# explorator_mainboard_v2_58mm_1_1.net
KiCad netlist of a schematic drawn in EAGLE
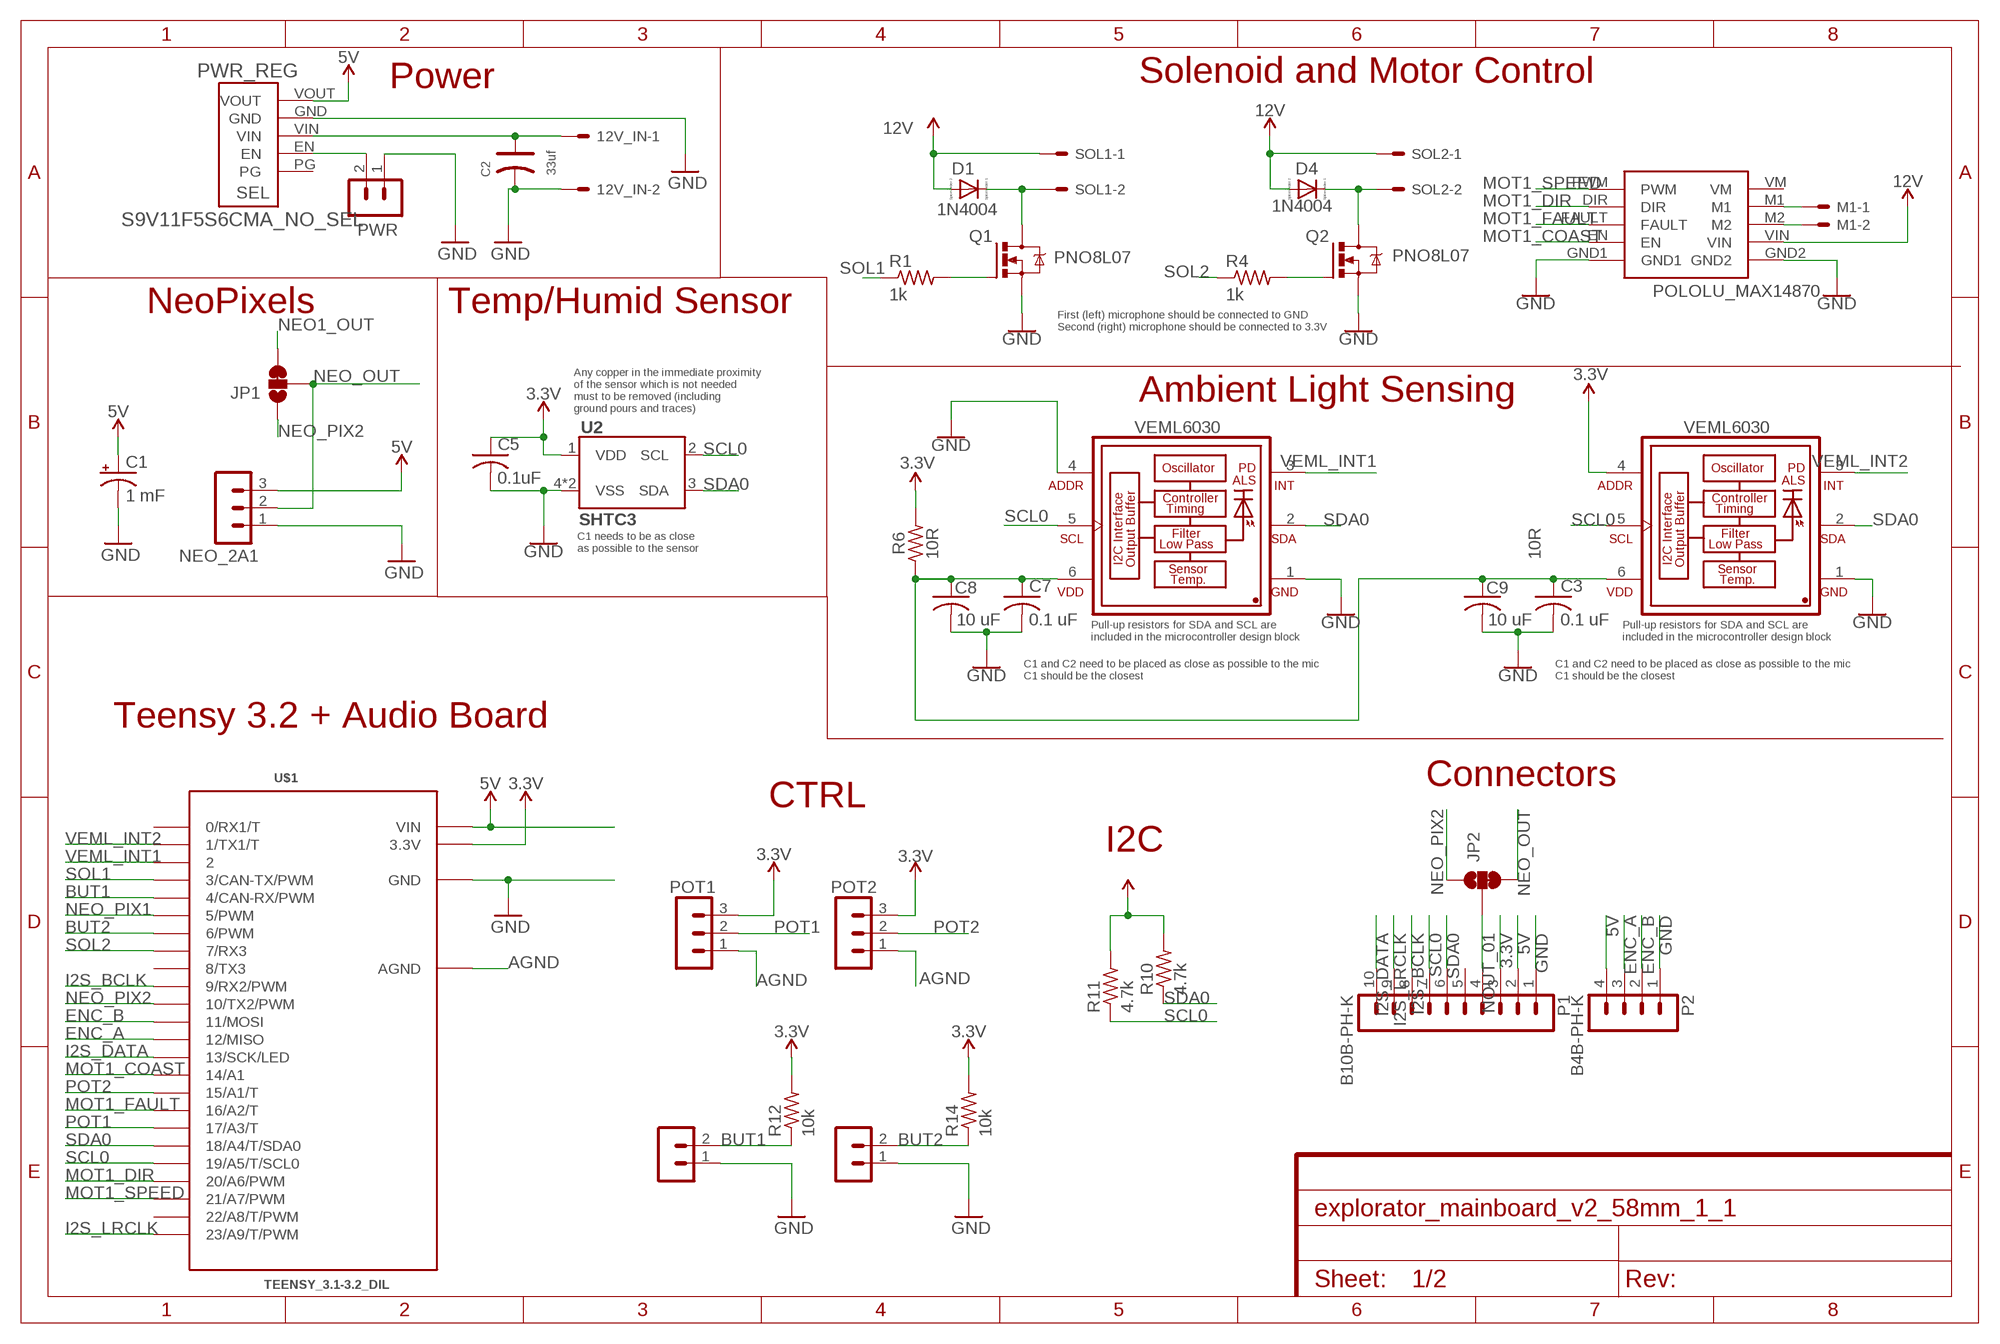
[diagram p0: schematic, sheet 1]
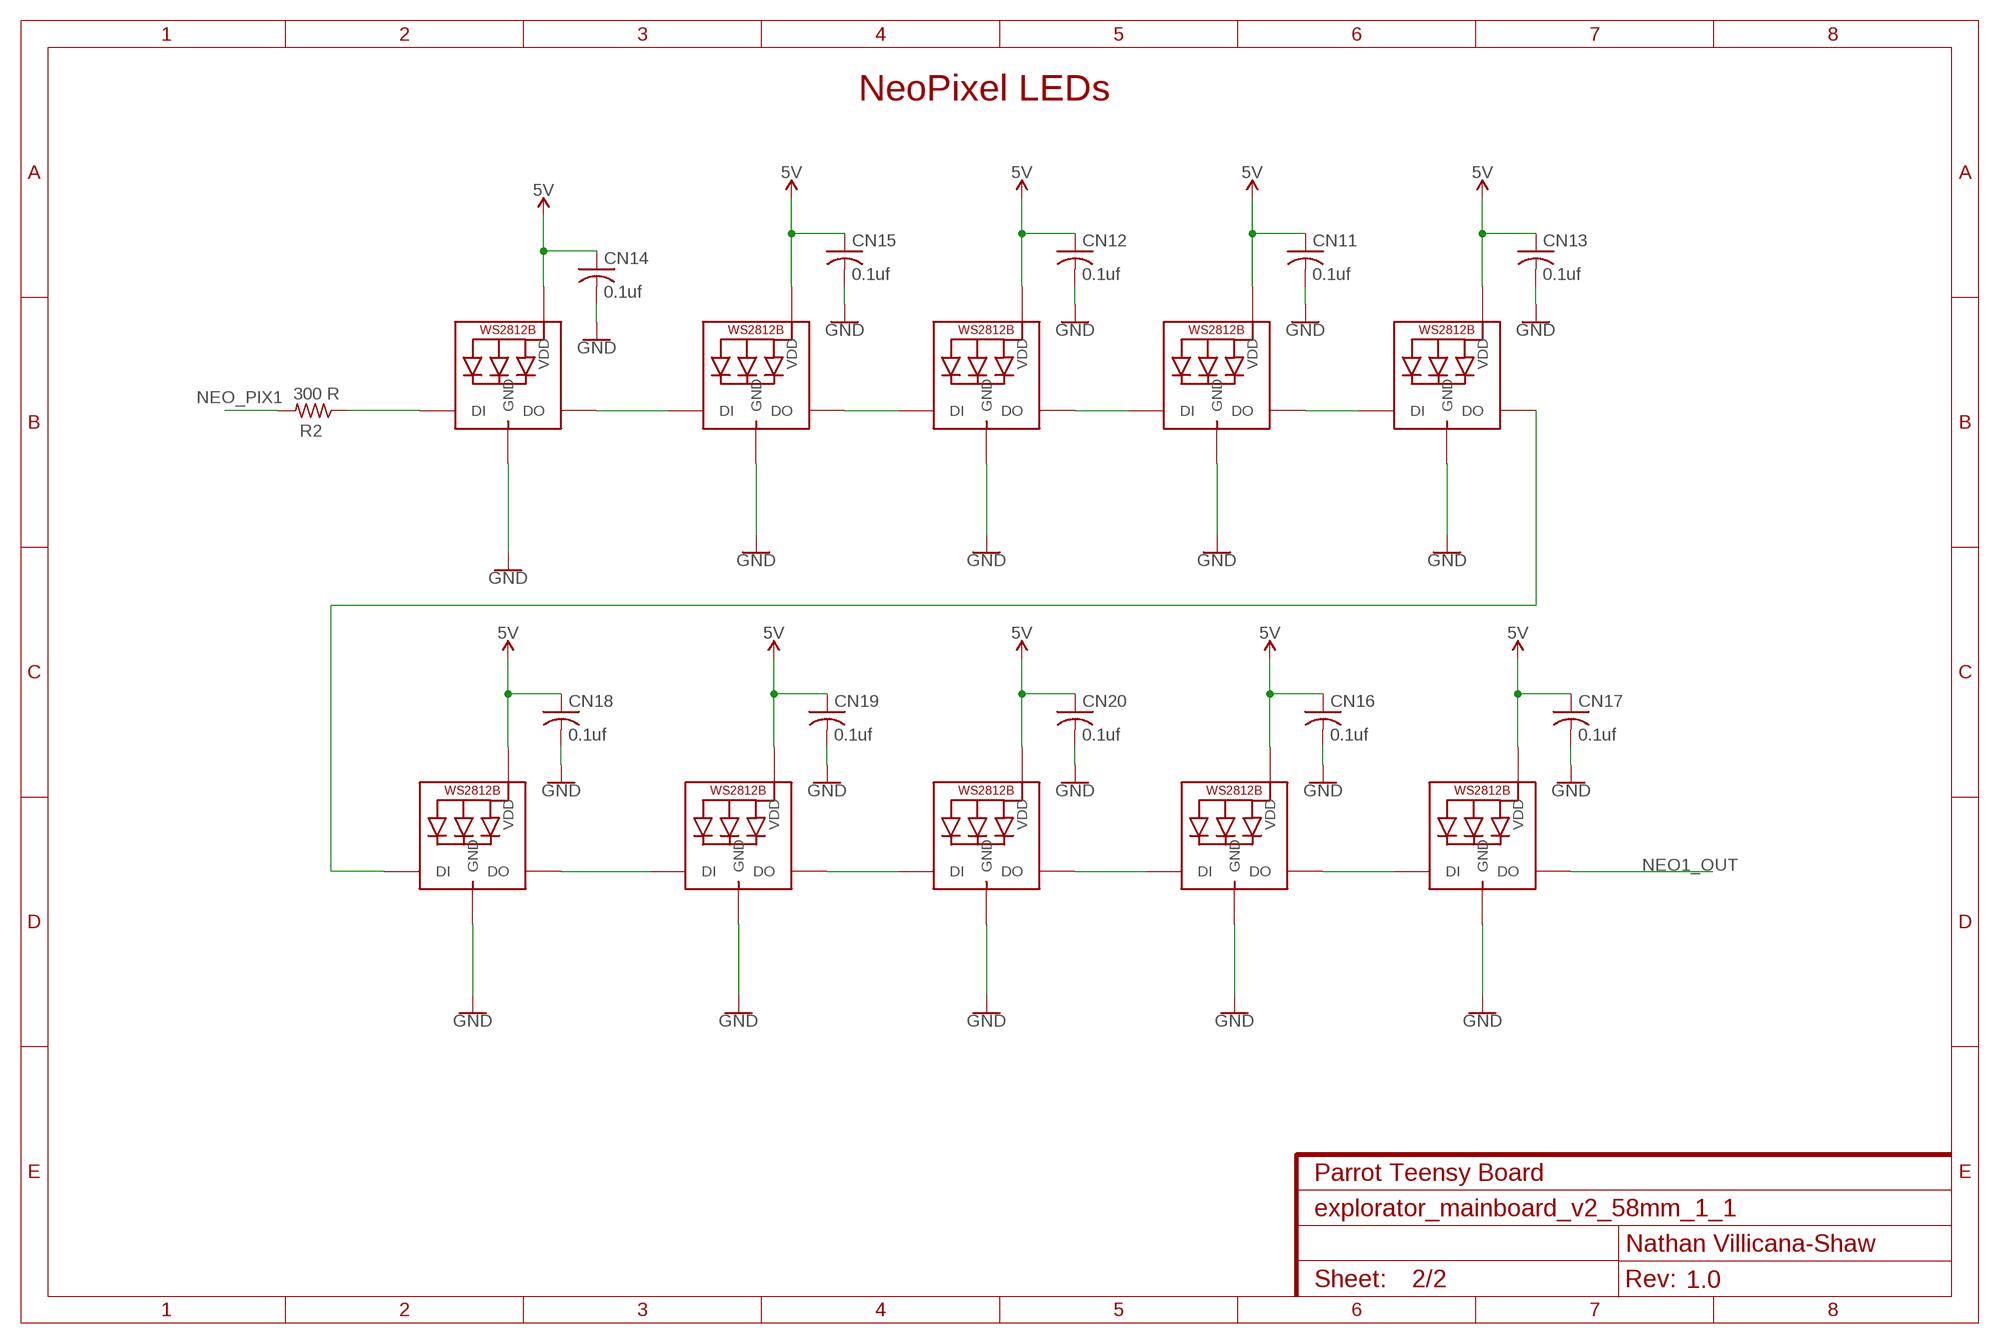
[diagram p1: schematic, sheet 2]

(export (version "E")
  (design (tool "Eeschema 10.0.6"))
  (components
    (comp (ref "12V_IN")
      (value "5566-2")
      (footprint "eagle-import:5566-2")
      (fields (field (name "MF") "MOLEX"))
      (libsource (lib "eagle-import") (part "5566-2"))
    )
    (comp (ref "BUT1")
      (value "B2B-PH-K")
      (footprint "eagle-import:B2B-PH-K")
      (libsource (lib "eagle-import") (part "B2B-PH-K"))
    )
    (comp (ref "BUT2")
      (value "B2B-PH-K")
      (footprint "eagle-import:B2B-PH-K")
      (libsource (lib "eagle-import") (part "B2B-PH-K"))
    )
    (comp (ref "C1")
      (value "1 mF")
      (footprint "eagle-import:UD-10X10_NICHICON")
      (libsource (lib "eagle-import") (part "CPOL-USUD-10X10"))
    )
    (comp (ref "C2")
      (value "33uf")
      (footprint "eagle-import:PC-D5.3MM")
      (fields (field (name "MPN") "KS 100uF/16V"))
      (libsource (lib "eagle-import") (part "DIP-ALUMINUM-47UF-16V(D5-H7MM)"))
    )
    (comp (ref "C3")
      (value "0.1 uF")
      (footprint "eagle-import:C0805")
      (libsource (lib "eagle-import") (part "C-USC0805"))
    )
    (comp (ref "C5")
      (value "0.1uF")
      (footprint "eagle-import:C0805")
      (libsource (lib "eagle-import") (part "C-USC0805"))
    )
    (comp (ref "C7")
      (value "0.1 uF")
      (footprint "eagle-import:C0805")
      (libsource (lib "eagle-import") (part "C-USC0805"))
    )
    (comp (ref "C8")
      (value "10 uF")
      (footprint "eagle-import:C0805")
      (libsource (lib "eagle-import") (part "C-USC0805"))
    )
    (comp (ref "C9")
      (value "10 uF")
      (footprint "eagle-import:C0805")
      (libsource (lib "eagle-import") (part "C-USC0805"))
    )
    (comp (ref "D1")
      (value "1N4004")
      (footprint "eagle-import:DIODE_DO35-7")
      (libsource (lib "eagle-import") (part "DIODE_E-DO35-7"))
    )
    (comp (ref "D4")
      (value "1N4004")
      (footprint "eagle-import:DIODE_DO35-7")
      (libsource (lib "eagle-import") (part "DIODE_E-DO35-7"))
    )
    (comp (ref "JP1")
      (value "JUMPER-SMT_3_1-NC_TRACE_SILK")
      (footprint "eagle-import:SMT-JUMPER_3_1-NC_TRACE_SILK")
      (libsource (lib "eagle-import") (part "JUMPER-SMT_3_1-NC_TRACE_SILK"))
    )
    (comp (ref "JP2")
      (value "JUMPER-SMT_3_1-NC_TRACE_SILK")
      (footprint "eagle-import:SMT-JUMPER_3_1-NC_TRACE_SILK")
      (libsource (lib "eagle-import") (part "JUMPER-SMT_3_1-NC_TRACE_SILK"))
    )
    (comp (ref "M1")
      (value "5566-2")
      (footprint "eagle-import:5566-2")
      (fields (field (name "MF") "MOLEX"))
      (libsource (lib "eagle-import") (part "5566-2"))
    )
    (comp (ref "MOT1")
      (value "POLOLU_MAX14870")
      (footprint "eagle-import:POLOLU_MAX14870")
      (libsource (lib "eagle-import") (part "POLOLU_MAX14870"))
    )
    (comp (ref "NEO_2A1")
      (value "B3B-PH-K")
      (footprint "eagle-import:B3B-PH-K")
      (libsource (lib "eagle-import") (part "B3B-PH-K"))
    )
    (comp (ref "P1")
      (value "B10B-PH-K")
      (footprint "eagle-import:B10B-PH-K")
      (libsource (lib "eagle-import") (part "B10B-PH-K"))
    )
    (comp (ref "P2")
      (value "B4B-PH-K")
      (footprint "eagle-import:B4B-PH-K")
      (libsource (lib "eagle-import") (part "B4B-PH-K"))
    )
    (comp (ref "POT1")
      (value "B3B-PH-K")
      (footprint "eagle-import:B3B-PH-K")
      (libsource (lib "eagle-import") (part "B3B-PH-K"))
    )
    (comp (ref "POT2")
      (value "B3B-PH-K")
      (footprint "eagle-import:B3B-PH-K")
      (libsource (lib "eagle-import") (part "B3B-PH-K"))
    )
    (comp (ref "PWR")
      (value "B2B-PH-K")
      (footprint "eagle-import:B2B-PH-K")
      (libsource (lib "eagle-import") (part "B2B-PH-K"))
    )
    (comp (ref "PWR_REG")
      (value "S9V11F5S6CMA_NO_SEL")
      (footprint "eagle-import:S9V11F3S5CMA_NO_SEL")
      (libsource (lib "eagle-import") (part "S9V11F5S6CMA_NO_SEL"))
    )
    (comp (ref "Q1")
      (value "PNO8L07")
      (footprint "eagle-import:TO220BV")
      (libsource (lib "eagle-import") (part "IRF540"))
    )
    (comp (ref "Q2")
      (value "PNO8L07")
      (footprint "eagle-import:TO220BV")
      (libsource (lib "eagle-import") (part "IRF540"))
    )
    (comp (ref "R1")
      (value "1k")
      (footprint "eagle-import:R0805")
      (libsource (lib "eagle-import") (part "rcl_334_R-US_R0805"))
    )
    (comp (ref "R4")
      (value "1k")
      (footprint "eagle-import:R0805")
      (libsource (lib "eagle-import") (part "rcl_334_R-US_R0805"))
    )
    (comp (ref "R6")
      (value "10 R")
      (footprint "eagle-import:R0805")
      (libsource (lib "eagle-import") (part "R-US_R0805"))
    )
    (comp (ref "R10")
      (value "4.7k")
      (footprint "eagle-import:R0805")
      (libsource (lib "eagle-import") (part "rcl_334_R-US_R0805"))
    )
    (comp (ref "R11")
      (value "4.7k")
      (footprint "eagle-import:R0805")
      (libsource (lib "eagle-import") (part "rcl_334_R-US_R0805"))
    )
    (comp (ref "R12")
      (value "10k")
      (footprint "eagle-import:R0805")
      (libsource (lib "eagle-import") (part "rcl_334_R-US_R0805"))
    )
    (comp (ref "R14")
      (value "10k")
      (footprint "eagle-import:R0805")
      (libsource (lib "eagle-import") (part "rcl_334_R-US_R0805"))
    )
    (comp (ref "SOL1")
      (value "5566-2")
      (footprint "eagle-import:5566-2")
      (fields (field (name "MF") "MOLEX"))
      (libsource (lib "eagle-import") (part "5566-2"))
    )
    (comp (ref "SOL2")
      (value "5566-2")
      (footprint "eagle-import:5566-2")
      (fields (field (name "MF") "MOLEX"))
      (libsource (lib "eagle-import") (part "5566-2"))
    )
    (comp (ref "U$1")
      (value "TEENSY_3.1-3.2_DIL")
      (footprint "eagle-import:TEENSY_3.0-3.2&LC_DIL")
      (libsource (lib "eagle-import") (part "TEENSY_3.1-3.2_DIL"))
    )
    (comp (ref "U2")
      (value "SHTC3")
      (footprint "eagle-import:SHTC3")
      (libsource (lib "eagle-import") (part "SHTC3"))
    )
    (comp (ref "VMEL1")
      (value "VEML6030")
      (footprint "eagle-import:VISHAY_VEML6030_2X2X0.87")
      (fields (field (name "MF") "Vishay Semiconductor") (field (name "MP") "VEML6030-GS15"))
      (libsource (lib "eagle-import") (part "VEML6030-GS15"))
    )
    (comp (ref "VMEL2")
      (value "VEML6030")
      (footprint "eagle-import:VISHAY_VEML6030_2X2X0.87")
      (fields (field (name "MF") "Vishay Semiconductor") (field (name "MP") "VEML6030-GS15"))
      (libsource (lib "eagle-import") (part "VEML6030-GS15"))
    )
    (comp (ref "CN11")
      (value "0.1uf")
      (footprint "eagle-import:C0805K")
      (libsource (lib "eagle-import") (part "resistor_348_C-USC0805K"))
    )
    (comp (ref "CN12")
      (value "0.1uf")
      (footprint "eagle-import:C0805K")
      (libsource (lib "eagle-import") (part "resistor_348_C-USC0805K"))
    )
    (comp (ref "CN13")
      (value "0.1uf")
      (footprint "eagle-import:C0805K")
      (libsource (lib "eagle-import") (part "resistor_348_C-USC0805K"))
    )
    (comp (ref "CN14")
      (value "0.1uf")
      (footprint "eagle-import:C0805K")
      (libsource (lib "eagle-import") (part "resistor_348_C-USC0805K"))
    )
    (comp (ref "CN15")
      (value "0.1uf")
      (footprint "eagle-import:C0805K")
      (libsource (lib "eagle-import") (part "resistor_348_C-USC0805K"))
    )
    (comp (ref "CN16")
      (value "0.1uf")
      (footprint "eagle-import:C0805K")
      (libsource (lib "eagle-import") (part "resistor_348_C-USC0805K"))
    )
    (comp (ref "CN17")
      (value "0.1uf")
      (footprint "eagle-import:C0805K")
      (libsource (lib "eagle-import") (part "resistor_348_C-USC0805K"))
    )
    (comp (ref "CN18")
      (value "0.1uf")
      (footprint "eagle-import:C0805K")
      (libsource (lib "eagle-import") (part "resistor_348_C-USC0805K"))
    )
    (comp (ref "CN19")
      (value "0.1uf")
      (footprint "eagle-import:C0805K")
      (libsource (lib "eagle-import") (part "resistor_348_C-USC0805K"))
    )
    (comp (ref "CN20")
      (value "0.1uf")
      (footprint "eagle-import:C0805K")
      (libsource (lib "eagle-import") (part "resistor_348_C-USC0805K"))
    )
    (comp (ref "NEO11")
      (value "WS2812B5050")
      (footprint "eagle-import:WS2812B")
      (libsource (lib "eagle-import") (part "WS2812B5050"))
    )
    (comp (ref "NEO12")
      (value "WS2812B5050")
      (footprint "eagle-import:WS2812B")
      (libsource (lib "eagle-import") (part "WS2812B5050"))
    )
    (comp (ref "NEO13")
      (value "WS2812B5050")
      (footprint "eagle-import:WS2812B")
      (libsource (lib "eagle-import") (part "WS2812B5050"))
    )
    (comp (ref "NEO14")
      (value "WS2812B5050")
      (footprint "eagle-import:WS2812B")
      (libsource (lib "eagle-import") (part "WS2812B5050"))
    )
    (comp (ref "NEO15")
      (value "WS2812B5050")
      (footprint "eagle-import:WS2812B")
      (libsource (lib "eagle-import") (part "WS2812B5050"))
    )
    (comp (ref "NEO16")
      (value "WS2812B5050")
      (footprint "eagle-import:WS2812B")
      (libsource (lib "eagle-import") (part "WS2812B5050"))
    )
    (comp (ref "NEO17")
      (value "WS2812B5050")
      (footprint "eagle-import:WS2812B")
      (libsource (lib "eagle-import") (part "WS2812B5050"))
    )
    (comp (ref "NEO18")
      (value "WS2812B5050")
      (footprint "eagle-import:WS2812B")
      (libsource (lib "eagle-import") (part "WS2812B5050"))
    )
    (comp (ref "NEO19")
      (value "WS2812B5050")
      (footprint "eagle-import:WS2812B")
      (libsource (lib "eagle-import") (part "WS2812B5050"))
    )
    (comp (ref "NEO20")
      (value "WS2812B5050")
      (footprint "eagle-import:WS2812B")
      (libsource (lib "eagle-import") (part "WS2812B5050"))
    )
    (comp (ref "R2")
      (value "300 R")
      (footprint "eagle-import:R0805")
      (libsource (lib "eagle-import") (part "R-US_R0805"))
    )
  )
  (nets
    (net (code "1") (name "3.3V") (class "Default")
      (node (ref "C5") (pin "1") (pinfunction "1_1") (pintype "passive"))
      (node (ref "P1") (pin "3") (pinfunction "3_3") (pintype "passive"))
      (node (ref "POT1") (pin "3") (pinfunction "3_3") (pintype "passive"))
      (node (ref "POT2") (pin "3") (pinfunction "3_3") (pintype "passive"))
      (node (ref "R10") (pin "2") (pinfunction "2_2") (pintype "passive"))
      (node (ref "R11") (pin "2") (pinfunction "2_2") (pintype "passive"))
      (node (ref "R12") (pin "2") (pinfunction "2_2") (pintype "passive"))
      (node (ref "R14") (pin "2") (pinfunction "2_2") (pintype "passive"))
      (node (ref "R6") (pin "2") (pinfunction "2_2") (pintype "passive"))
      (node (ref "U$1") (pin "3.3V") (pinfunction "3.3V_3.3V") (pintype "power_in"))
      (node (ref "U2") (pin "1") (pinfunction "VDD_1") (pintype "bidirectional"))
      (node (ref "VMEL2") (pin "4") (pinfunction "ADDR_4") (pintype "bidirectional"))
    )
    (net (code "2") (name "5V") (class "Default")
      (node (ref "C1") (pin "+") (pinfunction "+_+") (pintype "passive"))
      (node (ref "CN11") (pin "1") (pinfunction "1_1") (pintype "passive"))
      (node (ref "CN12") (pin "1") (pinfunction "1_1") (pintype "passive"))
      (node (ref "CN13") (pin "1") (pinfunction "1_1") (pintype "passive"))
      (node (ref "CN14") (pin "1") (pinfunction "1_1") (pintype "passive"))
      (node (ref "CN15") (pin "1") (pinfunction "1_1") (pintype "passive"))
      (node (ref "CN16") (pin "1") (pinfunction "1_1") (pintype "passive"))
      (node (ref "CN17") (pin "1") (pinfunction "1_1") (pintype "passive"))
      (node (ref "CN18") (pin "1") (pinfunction "1_1") (pintype "passive"))
      (node (ref "CN19") (pin "1") (pinfunction "1_1") (pintype "passive"))
      (node (ref "CN20") (pin "1") (pinfunction "1_1") (pintype "passive"))
      (node (ref "NEO11") (pin "1-VDD") (pinfunction "VDD_1-VDD") (pintype "power_in"))
      (node (ref "NEO12") (pin "1-VDD") (pinfunction "VDD_1-VDD") (pintype "power_in"))
      (node (ref "NEO13") (pin "1-VDD") (pinfunction "VDD_1-VDD") (pintype "power_in"))
      (node (ref "NEO14") (pin "1-VDD") (pinfunction "VDD_1-VDD") (pintype "power_in"))
      (node (ref "NEO15") (pin "1-VDD") (pinfunction "VDD_1-VDD") (pintype "power_in"))
      (node (ref "NEO16") (pin "1-VDD") (pinfunction "VDD_1-VDD") (pintype "power_in"))
      (node (ref "NEO17") (pin "1-VDD") (pinfunction "VDD_1-VDD") (pintype "power_in"))
      (node (ref "NEO18") (pin "1-VDD") (pinfunction "VDD_1-VDD") (pintype "power_in"))
      (node (ref "NEO19") (pin "1-VDD") (pinfunction "VDD_1-VDD") (pintype "power_in"))
      (node (ref "NEO20") (pin "1-VDD") (pinfunction "VDD_1-VDD") (pintype "power_in"))
      (node (ref "NEO_2A1") (pin "3") (pinfunction "3_3") (pintype "passive"))
      (node (ref "P1") (pin "2") (pinfunction "2_2") (pintype "passive"))
      (node (ref "P2") (pin "4") (pinfunction "4_4") (pintype "passive"))
      (node (ref "PWR_REG") (pin "VOUT") (pinfunction "VOUT_VOUT") (pintype "bidirectional"))
      (node (ref "U$1") (pin "VIN") (pinfunction "VIN_VIN") (pintype "power_in"))
    )
    (net (code "3") (name "12V") (class "Default")
      (node (ref "12V_IN") (pin "1") (pinfunction "S_1") (pintype "passive"))
      (node (ref "C2") (pin "+") (pinfunction "+_+") (pintype "passive"))
      (node (ref "D1") (pin "A") (pinfunction "C_A") (pintype "passive"))
      (node (ref "D4") (pin "A") (pinfunction "C_A") (pintype "passive"))
      (node (ref "MOT1") (pin "VIN") (pinfunction "VIN_VIN") (pintype "bidirectional"))
      (node (ref "PWR_REG") (pin "VIN") (pinfunction "VIN_VIN") (pintype "bidirectional"))
      (node (ref "SOL1") (pin "1") (pinfunction "S_1") (pintype "passive"))
      (node (ref "SOL2") (pin "1") (pinfunction "S_1") (pintype "passive"))
    )
    (net (code "4") (name "AGND") (class "Default")
      (node (ref "POT1") (pin "1") (pinfunction "1_1") (pintype "passive"))
      (node (ref "POT2") (pin "1") (pinfunction "1_1") (pintype "passive"))
      (node (ref "U$1") (pin "AGND") (pinfunction "AGND_AGND") (pintype "power_in"))
    )
    (net (code "5") (name "BUT1") (class "Default")
      (node (ref "BUT1") (pin "2") (pinfunction "2_2") (pintype "passive"))
      (node (ref "R12") (pin "1") (pinfunction "1_1") (pintype "passive"))
      (node (ref "U$1") (pin "4") (pinfunction "4/CAN-RX/PWM_4") (pintype "bidirectional"))
    )
    (net (code "6") (name "BUT2") (class "Default")
      (node (ref "BUT2") (pin "2") (pinfunction "2_2") (pintype "passive"))
      (node (ref "R14") (pin "1") (pinfunction "1_1") (pintype "passive"))
      (node (ref "U$1") (pin "6") (pinfunction "6/PWM_6") (pintype "bidirectional"))
    )
    (net (code "7") (name "ENC_A") (class "Default")
      (node (ref "P2") (pin "3") (pinfunction "3_3") (pintype "passive"))
      (node (ref "U$1") (pin "12") (pinfunction "12/MISO_12") (pintype "bidirectional"))
    )
    (net (code "8") (name "ENC_B") (class "Default")
      (node (ref "P2") (pin "2") (pinfunction "2_2") (pintype "passive"))
      (node (ref "U$1") (pin "11") (pinfunction "11/MOSI_11") (pintype "bidirectional"))
    )
    (net (code "9") (name "GND") (class "Default")
      (node (ref "12V_IN") (pin "2") (pinfunction "S_2") (pintype "passive"))
      (node (ref "BUT1") (pin "1") (pinfunction "1_1") (pintype "passive"))
      (node (ref "BUT2") (pin "1") (pinfunction "1_1") (pintype "passive"))
      (node (ref "C1") (pin "-") (pinfunction "-_-") (pintype "passive"))
      (node (ref "C2") (pin "-") (pinfunction "-_-") (pintype "passive"))
      (node (ref "C3") (pin "2") (pinfunction "2_2") (pintype "passive"))
      (node (ref "C5") (pin "2") (pinfunction "2_2") (pintype "passive"))
      (node (ref "C7") (pin "2") (pinfunction "2_2") (pintype "passive"))
      (node (ref "C8") (pin "2") (pinfunction "2_2") (pintype "passive"))
      (node (ref "C9") (pin "2") (pinfunction "2_2") (pintype "passive"))
      (node (ref "CN11") (pin "2") (pinfunction "2_2") (pintype "passive"))
      (node (ref "CN12") (pin "2") (pinfunction "2_2") (pintype "passive"))
      (node (ref "CN13") (pin "2") (pinfunction "2_2") (pintype "passive"))
      (node (ref "CN14") (pin "2") (pinfunction "2_2") (pintype "passive"))
      (node (ref "CN15") (pin "2") (pinfunction "2_2") (pintype "passive"))
      (node (ref "CN16") (pin "2") (pinfunction "2_2") (pintype "passive"))
      (node (ref "CN17") (pin "2") (pinfunction "2_2") (pintype "passive"))
      (node (ref "CN18") (pin "2") (pinfunction "2_2") (pintype "passive"))
      (node (ref "CN19") (pin "2") (pinfunction "2_2") (pintype "passive"))
      (node (ref "CN20") (pin "2") (pinfunction "2_2") (pintype "passive"))
      (node (ref "MOT1") (pin "GND1") (pinfunction "GND1_GND1") (pintype "bidirectional"))
      (node (ref "MOT1") (pin "GND2") (pinfunction "GND2_GND2") (pintype "bidirectional"))
      (node (ref "NEO11") (pin "3-GND") (pinfunction "GND_3-GND") (pintype "power_in"))
      (node (ref "NEO12") (pin "3-GND") (pinfunction "GND_3-GND") (pintype "power_in"))
      (node (ref "NEO13") (pin "3-GND") (pinfunction "GND_3-GND") (pintype "power_in"))
      (node (ref "NEO14") (pin "3-GND") (pinfunction "GND_3-GND") (pintype "power_in"))
      (node (ref "NEO15") (pin "3-GND") (pinfunction "GND_3-GND") (pintype "power_in"))
      (node (ref "NEO16") (pin "3-GND") (pinfunction "GND_3-GND") (pintype "power_in"))
      (node (ref "NEO17") (pin "3-GND") (pinfunction "GND_3-GND") (pintype "power_in"))
      (node (ref "NEO18") (pin "3-GND") (pinfunction "GND_3-GND") (pintype "power_in"))
      (node (ref "NEO19") (pin "3-GND") (pinfunction "GND_3-GND") (pintype "power_in"))
      (node (ref "NEO20") (pin "3-GND") (pinfunction "GND_3-GND") (pintype "power_in"))
      (node (ref "NEO_2A1") (pin "1") (pinfunction "1_1") (pintype "passive"))
      (node (ref "P1") (pin "1") (pinfunction "1_1") (pintype "passive"))
      (node (ref "P2") (pin "1") (pinfunction "1_1") (pintype "passive"))
      (node (ref "PWR") (pin "1") (pinfunction "1_1") (pintype "passive"))
      (node (ref "PWR_REG") (pin "GND") (pinfunction "GND_GND") (pintype "bidirectional"))
      (node (ref "Q1") (pin "S") (pinfunction "S_S") (pintype "passive"))
      (node (ref "Q2") (pin "S") (pinfunction "S_S") (pintype "passive"))
      (node (ref "U$1") (pin "GND") (pinfunction "GND_GND") (pintype "power_in"))
      (node (ref "U2") (pin "4") (pinfunction "VSS_4") (pintype "bidirectional"))
      (node (ref "U2") (pin "5") (pinfunction "VSS_5") (pintype "bidirectional"))
      (node (ref "VMEL1") (pin "1") (pinfunction "GND_1") (pintype "power_in"))
      (node (ref "VMEL1") (pin "4") (pinfunction "ADDR_4") (pintype "bidirectional"))
      (node (ref "VMEL2") (pin "1") (pinfunction "GND_1") (pintype "power_in"))
    )
    (net (code "10") (name "I2S_BCLK") (class "Default")
      (node (ref "P1") (pin "8") (pinfunction "8_8") (pintype "passive"))
      (node (ref "U$1") (pin "9") (pinfunction "9/RX2/PWM_9") (pintype "bidirectional"))
    )
    (net (code "11") (name "I2S_DATA") (class "Default")
      (node (ref "P1") (pin "10") (pinfunction "10_10") (pintype "passive"))
      (node (ref "U$1") (pin "13") (pinfunction "13/SCK/LED_13") (pintype "bidirectional"))
    )
    (net (code "12") (name "I2S_LRCLK") (class "Default")
      (node (ref "P1") (pin "9") (pinfunction "9_9") (pintype "passive"))
      (node (ref "U$1") (pin "23/A9") (pinfunction "23/A9/T/PWM_23/A9") (pintype "bidirectional"))
    )
    (net (code "13") (name "MOT1_COAST") (class "Default")
      (node (ref "MOT1") (pin "EN") (pinfunction "EN_EN") (pintype "bidirectional"))
      (node (ref "U$1") (pin "14/A0") (pinfunction "14/A1_14/A0") (pintype "bidirectional"))
    )
    (net (code "14") (name "MOT1_DIR") (class "Default")
      (node (ref "MOT1") (pin "DIR") (pinfunction "DIR_DIR") (pintype "bidirectional"))
      (node (ref "U$1") (pin "20/A6") (pinfunction "20/A6/PWM_20/A6") (pintype "bidirectional"))
    )
    (net (code "15") (name "MOT1_FAULT") (class "Default")
      (node (ref "MOT1") (pin "FAULT") (pinfunction "FAULT_FAULT") (pintype "bidirectional"))
      (node (ref "U$1") (pin "16/A2") (pinfunction "16/A2/T_16/A2") (pintype "bidirectional"))
    )
    (net (code "16") (name "MOT1_SPEED") (class "Default")
      (node (ref "MOT1") (pin "PWM") (pinfunction "PWM_PWM") (pintype "bidirectional"))
      (node (ref "U$1") (pin "21/A7") (pinfunction "21/A7/PWM_21/A7") (pintype "bidirectional"))
    )
    (net (code "17") (name "NEO1_OUT") (class "Default")
      (node (ref "JP1") (pin "3") (pinfunction "3_3") (pintype "passive"))
      (node (ref "NEO17") (pin "2-DOUT") (pinfunction "DO_2-DOUT") (pintype "output"))
    )
    (net (code "18") (name "NEO_OUT") (class "Default")
      (node (ref "JP1") (pin "2") (pinfunction "2_2") (pintype "passive"))
      (node (ref "JP2") (pin "3") (pinfunction "3_3") (pintype "passive"))
      (node (ref "NEO_2A1") (pin "2") (pinfunction "2_2") (pintype "passive"))
    )
    (net (code "19") (name "NEO_PIX1") (class "Default")
      (node (ref "R2") (pin "2") (pinfunction "2_2") (pintype "passive"))
      (node (ref "U$1") (pin "5") (pinfunction "5/PWM_5") (pintype "bidirectional"))
    )
    (net (code "20") (name "NEO_PIX2") (class "Default")
      (node (ref "JP1") (pin "1") (pinfunction "1_1") (pintype "passive"))
      (node (ref "JP2") (pin "1") (pinfunction "1_1") (pintype "passive"))
      (node (ref "U$1") (pin "10") (pinfunction "10/TX2/PWM_10") (pintype "bidirectional"))
    )
    (net (code "21") (name "NOUT_01") (class "Default")
      (node (ref "JP2") (pin "2") (pinfunction "2_2") (pintype "passive"))
      (node (ref "P1") (pin "4") (pinfunction "4_4") (pintype "passive"))
    )
    (net (code "22") (name "Net-(D1-A)") (class "Default")
      (node (ref "D1") (pin "C") (pinfunction "A_C") (pintype "passive"))
      (node (ref "Q1") (pin "D") (pinfunction "D_D") (pintype "passive"))
      (node (ref "SOL1") (pin "2") (pinfunction "S_2") (pintype "passive"))
    )
    (net (code "23") (name "Net-(D4-A)") (class "Default")
      (node (ref "D4") (pin "C") (pinfunction "A_C") (pintype "passive"))
      (node (ref "Q2") (pin "D") (pinfunction "D_D") (pintype "passive"))
      (node (ref "SOL2") (pin "2") (pinfunction "S_2") (pintype "passive"))
    )
    (net (code "24") (name "Net-(M1A-S)") (class "Default")
      (node (ref "M1") (pin "1") (pinfunction "S_1") (pintype "passive"))
      (node (ref "MOT1") (pin "M1") (pinfunction "M1_M1") (pintype "bidirectional"))
    )
    (net (code "25") (name "Net-(M1B-S)") (class "Default")
      (node (ref "M1") (pin "2") (pinfunction "S_2") (pintype "passive"))
      (node (ref "MOT1") (pin "M2") (pinfunction "M2_M2") (pintype "bidirectional"))
    )
    (net (code "26") (name "Net-(NEO11-DI)") (class "Default")
      (node (ref "NEO11") (pin "4-DIN") (pinfunction "DI_4-DIN") (pintype "input"))
      (node (ref "NEO12") (pin "2-DOUT") (pinfunction "DO_2-DOUT") (pintype "output"))
    )
    (net (code "27") (name "Net-(NEO11-DO)") (class "Default")
      (node (ref "NEO11") (pin "2-DOUT") (pinfunction "DO_2-DOUT") (pintype "output"))
      (node (ref "NEO13") (pin "4-DIN") (pinfunction "DI_4-DIN") (pintype "input"))
    )
    (net (code "28") (name "Net-(NEO12-DI)") (class "Default")
      (node (ref "NEO12") (pin "4-DIN") (pinfunction "DI_4-DIN") (pintype "input"))
      (node (ref "NEO15") (pin "2-DOUT") (pinfunction "DO_2-DOUT") (pintype "output"))
    )
    (net (code "29") (name "Net-(NEO13-DO)") (class "Default")
      (node (ref "NEO13") (pin "2-DOUT") (pinfunction "DO_2-DOUT") (pintype "output"))
      (node (ref "NEO18") (pin "4-DIN") (pinfunction "DI_4-DIN") (pintype "input"))
    )
    (net (code "30") (name "Net-(NEO14-DI)") (class "Default")
      (node (ref "NEO14") (pin "4-DIN") (pinfunction "DI_4-DIN") (pintype "input"))
      (node (ref "R2") (pin "1") (pinfunction "1_1") (pintype "passive"))
    )
    (net (code "31") (name "Net-(NEO14-DO)") (class "Default")
      (node (ref "NEO14") (pin "2-DOUT") (pinfunction "DO_2-DOUT") (pintype "output"))
      (node (ref "NEO15") (pin "4-DIN") (pinfunction "DI_4-DIN") (pintype "input"))
    )
    (net (code "32") (name "Net-(NEO16-DI)") (class "Default")
      (node (ref "NEO16") (pin "4-DIN") (pinfunction "DI_4-DIN") (pintype "input"))
      (node (ref "NEO20") (pin "2-DOUT") (pinfunction "DO_2-DOUT") (pintype "output"))
    )
    (net (code "33") (name "Net-(NEO16-DO)") (class "Default")
      (node (ref "NEO16") (pin "2-DOUT") (pinfunction "DO_2-DOUT") (pintype "output"))
      (node (ref "NEO17") (pin "4-DIN") (pinfunction "DI_4-DIN") (pintype "input"))
    )
    (net (code "34") (name "Net-(NEO18-DO)") (class "Default")
      (node (ref "NEO18") (pin "2-DOUT") (pinfunction "DO_2-DOUT") (pintype "output"))
      (node (ref "NEO19") (pin "4-DIN") (pinfunction "DI_4-DIN") (pintype "input"))
    )
    (net (code "35") (name "Net-(NEO19-DO)") (class "Default")
      (node (ref "NEO19") (pin "2-DOUT") (pinfunction "DO_2-DOUT") (pintype "output"))
      (node (ref "NEO20") (pin "4-DIN") (pinfunction "DI_4-DIN") (pintype "input"))
    )
    (net (code "36") (name "Net-(PWR-Pad2)") (class "Default")
      (node (ref "PWR") (pin "2") (pinfunction "2_2") (pintype "passive"))
      (node (ref "PWR_REG") (pin "EN") (pinfunction "EN_EN") (pintype "bidirectional"))
    )
    (net (code "37") (name "Net-(Q1-PadG)") (class "Default")
      (node (ref "Q1") (pin "G") (pinfunction "G_G") (pintype "passive"))
      (node (ref "R1") (pin "2") (pinfunction "2_2") (pintype "passive"))
    )
    (net (code "38") (name "Net-(Q2-PadG)") (class "Default")
      (node (ref "Q2") (pin "G") (pinfunction "G_G") (pintype "passive"))
      (node (ref "R4") (pin "2") (pinfunction "2_2") (pintype "passive"))
    )
    (net (code "39") (name "Net-(VMEL1-VDD)") (class "Default")
      (node (ref "C3") (pin "1") (pinfunction "1_1") (pintype "passive"))
      (node (ref "C7") (pin "1") (pinfunction "1_1") (pintype "passive"))
      (node (ref "C8") (pin "1") (pinfunction "1_1") (pintype "passive"))
      (node (ref "C9") (pin "1") (pinfunction "1_1") (pintype "passive"))
      (node (ref "R6") (pin "1") (pinfunction "1_1") (pintype "passive"))
      (node (ref "VMEL1") (pin "6") (pinfunction "VDD_6") (pintype "power_in"))
      (node (ref "VMEL2") (pin "6") (pinfunction "VDD_6") (pintype "power_in"))
    )
    (net (code "40") (name "POT1") (class "Default")
      (node (ref "POT1") (pin "2") (pinfunction "2_2") (pintype "passive"))
      (node (ref "U$1") (pin "17/A3") (pinfunction "17/A3/T_17/A3") (pintype "bidirectional"))
    )
    (net (code "41") (name "POT2") (class "Default")
      (node (ref "POT2") (pin "2") (pinfunction "2_2") (pintype "passive"))
      (node (ref "U$1") (pin "15/A1") (pinfunction "15/A1/T_15/A1") (pintype "bidirectional"))
    )
    (net (code "42") (name "SCL0") (class "Default")
      (node (ref "P1") (pin "7") (pinfunction "7_7") (pintype "passive"))
      (node (ref "R11") (pin "1") (pinfunction "1_1") (pintype "passive"))
      (node (ref "U$1") (pin "19/A5") (pinfunction "19/A5/T/SCL0_19/A5") (pintype "bidirectional"))
      (node (ref "U2") (pin "2") (pinfunction "SCL_2") (pintype "bidirectional"))
      (node (ref "VMEL1") (pin "5") (pinfunction "SCL_5") (pintype "input"))
      (node (ref "VMEL2") (pin "5") (pinfunction "SCL_5") (pintype "input"))
    )
    (net (code "43") (name "SDA0") (class "Default")
      (node (ref "P1") (pin "6") (pinfunction "6_6") (pintype "passive"))
      (node (ref "R10") (pin "1") (pinfunction "1_1") (pintype "passive"))
      (node (ref "U$1") (pin "18/A4") (pinfunction "18/A4/T/SDA0_18/A4") (pintype "bidirectional"))
      (node (ref "U2") (pin "3") (pinfunction "SDA_3") (pintype "bidirectional"))
      (node (ref "VMEL1") (pin "2") (pinfunction "SDA_2") (pintype "bidirectional"))
      (node (ref "VMEL2") (pin "2") (pinfunction "SDA_2") (pintype "bidirectional"))
    )
    (net (code "44") (name "SOL1") (class "Default")
      (node (ref "R1") (pin "1") (pinfunction "1_1") (pintype "passive"))
      (node (ref "U$1") (pin "3") (pinfunction "3/CAN-TX/PWM_3") (pintype "bidirectional"))
    )
    (net (code "45") (name "SOL2") (class "Default")
      (node (ref "R4") (pin "1") (pinfunction "1_1") (pintype "passive"))
      (node (ref "U$1") (pin "7") (pinfunction "7/RX3_7") (pintype "bidirectional"))
    )
    (net (code "46") (name "VEML_INT1") (class "Default")
      (node (ref "U$1") (pin "2") (pinfunction "2_2") (pintype "bidirectional"))
      (node (ref "VMEL1") (pin "3") (pinfunction "INT_3") (pintype "output"))
    )
    (net (code "47") (name "VEML_INT2") (class "Default")
      (node (ref "U$1") (pin "1") (pinfunction "1/TX1/T_1") (pintype "bidirectional"))
      (node (ref "VMEL2") (pin "3") (pinfunction "INT_3") (pintype "output"))
    )
    (net (code "48") (name "unconnected-(MOT1-PadVM)") (class "Default")
      (node (ref "MOT1") (pin "VM") (pinfunction "VM_VM") (pintype "bidirectional"))
    )
    (net (code "49") (name "unconnected-(P1-Pad5)") (class "Default")
      (node (ref "P1") (pin "5") (pinfunction "5_5") (pintype "passive"))
    )
    (net (code "50") (name "unconnected-(PWR_REG-PadPG)") (class "Default")
      (node (ref "PWR_REG") (pin "PG") (pinfunction "PG_PG") (pintype "bidirectional"))
    )
    (net (code "51") (name "unconnected-(U$1-0{slash}RX1{slash}T-Pad0)") (class "Default")
      (node (ref "U$1") (pin "0") (pinfunction "0/RX1/T_0") (pintype "bidirectional"))
    )
    (net (code "52") (name "unconnected-(U$1-8{slash}TX3-Pad8)") (class "Default")
      (node (ref "U$1") (pin "8") (pinfunction "8/TX3_8") (pintype "bidirectional"))
    )
    (net (code "53") (name "unconnected-(U$1-22{slash}A8{slash}T{slash}PWM-Pad22{slash}A8)") (class "Default")
      (node (ref "U$1") (pin "22/A8") (pinfunction "22/A8/T/PWM_22/A8") (pintype "bidirectional"))
    )
  )
)
